# StepperController.net
KiCad netlist of a schematic drawn in Altium Designer
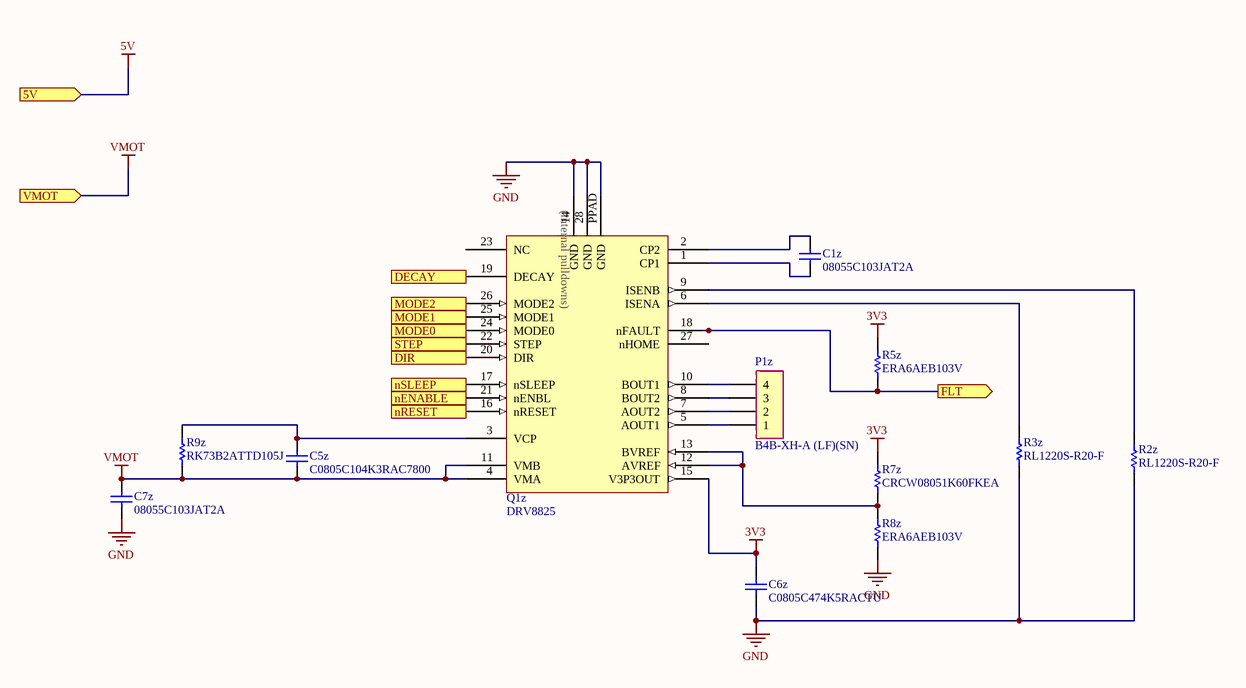
[diagram p0: StepperController.SchDoc]

(export (version "E")
  (design (tool "Eeschema 10.0.6"))
  (components
    (comp (ref "C1z")
      (value "08055C103JAT2A")
      (footprint "CAPC2013X94X50ML20T25")
      (fields (field (name "MANUFACTURER") "AVX Interconnect / Elco"))
      (libsource (lib "Altium Content Vault") (part "CAP"))
    )
    (comp (ref "C5z")
      (value "C0805C104K3RAC7800")
      (footprint "CAPC2013X145X50ML20T25")
      (fields (field (name "MANUFACTURER") "Kemet"))
      (libsource (lib "Altium Content Vault") (part "CAP"))
    )
    (comp (ref "C6z")
      (value "C0805C474K5RACTU")
      (footprint "CAPC2013X110X50NL20T25")
      (fields (field (name "MANUFACTURER") "Kemet"))
      (libsource (lib "Altium Content Vault") (part "CAP"))
    )
    (comp (ref "C7z")
      (value "08055C103JAT2A")
      (footprint "CAPC2013X94X50ML20T25")
      (fields (field (name "MANUFACTURER") "AVX Interconnect / Elco"))
      (libsource (lib "Altium Content Vault") (part "CAP"))
    )
    (comp (ref "P1z")
      (value "B4B-XH-A (LF)(SN)")
      (footprint "B4B-XH-A (LF)(SN)")
      (description "Wire-to-board connector, vertical, 2.5mm, 4 contacts")
      (libsource (lib "JCULibrary_AS2") (part "B4B-XH-A (LF)(SN) Wire-to-board connector"))
    )
    (comp (ref "Q1z")
      (value "DRV8825")
      (footprint "DRV8825 HTSSOP")
      (description "TI DRV8825 Stepper Motor Controller IC")
      (libsource (lib "JCULibrary_AS2") (part "Stepper motor driver DRV8825"))
    )
    (comp (ref "R2z")
      (value "RL1220S-R20-F")
      (footprint "RESC2013X50X40ML20T20")
      (fields (field (name "MANUFACTURER") "Susumu"))
      (libsource (lib "Altium Content Vault") (part "RES"))
    )
    (comp (ref "R3z")
      (value "RL1220S-R20-F")
      (footprint "RESC2013X50X40ML20T20")
      (fields (field (name "MANUFACTURER") "Susumu"))
      (libsource (lib "Altium Content Vault") (part "RES"))
    )
    (comp (ref "R5z")
      (value "ERA6AEB103V")
      (footprint "RESC2013X60X40ML20T25")
      (fields (field (name "MANUFACTURER") "Panasonic"))
      (libsource (lib "Altium Content Vault") (part "RES"))
    )
    (comp (ref "R7z")
      (value "CRCW08051K60FKEA")
      (footprint "RESC2013X50X30NL20T20")
      (fields (field (name "MANUFACTURER") "Vishay Dale"))
      (libsource (lib "Altium Content Vault") (part "RES"))
    )
    (comp (ref "R8z")
      (value "ERA6AEB103V")
      (footprint "RESC2013X60X40ML20T25")
      (fields (field (name "MANUFACTURER") "Panasonic"))
      (libsource (lib "Altium Content Vault") (part "RES"))
    )
    (comp (ref "R9z")
      (value "RK73B2ATTD105J")
      (footprint "RESC2013X60X30NL20T20")
      (fields (field (name "MANUFACTURER") "KOA Speer"))
      (libsource (lib "Altium Content Vault") (part "RES"))
    )
  )
  (nets
    (net (code "1") (name "/DECAY") (class "Default")
      (node (ref "Q1z") (pin "19") (pinfunction "DECAY_19") (pintype "passive"))
    )
    (net (code "2") (name "/DIR") (class "Default")
      (node (ref "Q1z") (pin "20") (pinfunction "DIR_20") (pintype "input"))
    )
    (net (code "3") (name "/FLT") (class "Default")
      (node (ref "Q1z") (pin "18") (pinfunction "nFAULT_18") (pintype "open_collector"))
      (node (ref "R5z") (pin "2") (pinfunction "2_2") (pintype "passive"))
    )
    (net (code "4") (name "/MODE0") (class "Default")
      (node (ref "Q1z") (pin "24") (pinfunction "MODE0_24") (pintype "input"))
    )
    (net (code "5") (name "/MODE1") (class "Default")
      (node (ref "Q1z") (pin "25") (pinfunction "MODE1_25") (pintype "input"))
    )
    (net (code "6") (name "/MODE2") (class "Default")
      (node (ref "Q1z") (pin "26") (pinfunction "MODE2_26") (pintype "input"))
    )
    (net (code "7") (name "/STEP") (class "Default")
      (node (ref "Q1z") (pin "22") (pinfunction "STEP_22") (pintype "input"))
    )
    (net (code "8") (name "/nENABLE") (class "Default")
      (node (ref "Q1z") (pin "21") (pinfunction "nENBL_21") (pintype "input"))
    )
    (net (code "9") (name "/nRESET") (class "Default")
      (node (ref "Q1z") (pin "16") (pinfunction "nRESET_16") (pintype "input"))
    )
    (net (code "10") (name "/nSLEEP") (class "Default")
      (node (ref "Q1z") (pin "17") (pinfunction "nSLEEP_17") (pintype "input"))
    )
    (net (code "11") (name "3V3") (class "Default")
      (node (ref "C6z") (pin "2") (pinfunction "2_2") (pintype "passive"))
      (node (ref "Q1z") (pin "15") (pinfunction "V3P3OUT_15") (pintype "output"))
      (node (ref "R5z") (pin "1") (pinfunction "1_1") (pintype "passive"))
      (node (ref "R7z") (pin "2") (pinfunction "2_2") (pintype "passive"))
    )
    (net (code "13") (name "GND") (class "Default")
      (node (ref "C6z") (pin "1") (pinfunction "1_1") (pintype "passive"))
      (node (ref "C7z") (pin "1") (pinfunction "1_1") (pintype "passive"))
      (node (ref "Q1z") (pin "14") (pinfunction "GND_14") (pintype "power_in"))
      (node (ref "Q1z") (pin "28") (pinfunction "GND_28") (pintype "power_in"))
      (node (ref "Q1z") (pin "PPAD") (pinfunction "GND_PPAD") (pintype "power_in"))
      (node (ref "R2z") (pin "1") (pinfunction "1_1") (pintype "passive"))
      (node (ref "R3z") (pin "1") (pinfunction "1_1") (pintype "passive"))
      (node (ref "R8z") (pin "1") (pinfunction "1_1") (pintype "passive"))
    )
    (net (code "14") (name "Net-(Q1z-AOUT1)") (class "Default")
      (node (ref "P1z") (pin "1") (pinfunction "1_1") (pintype "passive"))
      (node (ref "Q1z") (pin "5") (pinfunction "AOUT1_5") (pintype "output"))
    )
    (net (code "15") (name "Net-(Q1z-AOUT2)") (class "Default")
      (node (ref "P1z") (pin "2") (pinfunction "2_2") (pintype "passive"))
      (node (ref "Q1z") (pin "7") (pinfunction "AOUT2_7") (pintype "output"))
    )
    (net (code "16") (name "Net-(Q1z-AVREF)") (class "Default")
      (node (ref "Q1z") (pin "12") (pinfunction "AVREF_12") (pintype "input"))
      (node (ref "Q1z") (pin "13") (pinfunction "BVREF_13") (pintype "input"))
      (node (ref "R7z") (pin "1") (pinfunction "1_1") (pintype "passive"))
      (node (ref "R8z") (pin "2") (pinfunction "2_2") (pintype "passive"))
    )
    (net (code "17") (name "Net-(Q1z-BOUT1)") (class "Default")
      (node (ref "P1z") (pin "4") (pinfunction "4_4") (pintype "passive"))
      (node (ref "Q1z") (pin "10") (pinfunction "BOUT1_10") (pintype "output"))
    )
    (net (code "18") (name "Net-(Q1z-BOUT2)") (class "Default")
      (node (ref "P1z") (pin "3") (pinfunction "3_3") (pintype "passive"))
      (node (ref "Q1z") (pin "8") (pinfunction "BOUT2_8") (pintype "output"))
    )
    (net (code "19") (name "Net-(Q1z-CP1)") (class "Default")
      (node (ref "C1z") (pin "1") (pinfunction "1_1") (pintype "passive"))
      (node (ref "Q1z") (pin "1") (pinfunction "CP1_1") (pintype "power_in"))
    )
    (net (code "20") (name "Net-(Q1z-CP2)") (class "Default")
      (node (ref "C1z") (pin "2") (pinfunction "2_2") (pintype "passive"))
      (node (ref "Q1z") (pin "2") (pinfunction "CP2_2") (pintype "power_in"))
    )
    (net (code "21") (name "Net-(Q1z-ISENA)") (class "Default")
      (node (ref "Q1z") (pin "6") (pinfunction "ISENA_6") (pintype "output"))
      (node (ref "R3z") (pin "2") (pinfunction "2_2") (pintype "passive"))
    )
    (net (code "22") (name "Net-(Q1z-ISENB)") (class "Default")
      (node (ref "Q1z") (pin "9") (pinfunction "ISENB_9") (pintype "output"))
      (node (ref "R2z") (pin "2") (pinfunction "2_2") (pintype "passive"))
    )
    (net (code "23") (name "Net-(Q1z-VCP)") (class "Default")
      (node (ref "C5z") (pin "1") (pinfunction "1_1") (pintype "passive"))
      (node (ref "Q1z") (pin "3") (pinfunction "VCP_3") (pintype "power_in"))
      (node (ref "R9z") (pin "2") (pinfunction "2_2") (pintype "passive"))
    )
    (net (code "24") (name "VMOT") (class "Default")
      (node (ref "C5z") (pin "2") (pinfunction "2_2") (pintype "passive"))
      (node (ref "C7z") (pin "2") (pinfunction "2_2") (pintype "passive"))
      (node (ref "Q1z") (pin "11") (pinfunction "VMB_11") (pintype "power_in"))
      (node (ref "Q1z") (pin "4") (pinfunction "VMA_4") (pintype "power_in"))
      (node (ref "R9z") (pin "1") (pinfunction "1_1") (pintype "passive"))
    )
    (net (code "25") (name "unconnected-(Q1z-NC-Pad23)") (class "Default")
      (node (ref "Q1z") (pin "23") (pinfunction "NC_23") (pintype "passive"))
    )
    (net (code "26") (name "unconnected-(Q1z-nHOME-Pad27)") (class "Default")
      (node (ref "Q1z") (pin "27") (pinfunction "nHOME_27") (pintype "open_collector"))
    )
  )
)
